# omca.net
KiCad netlist of a schematic drawn in EAGLE
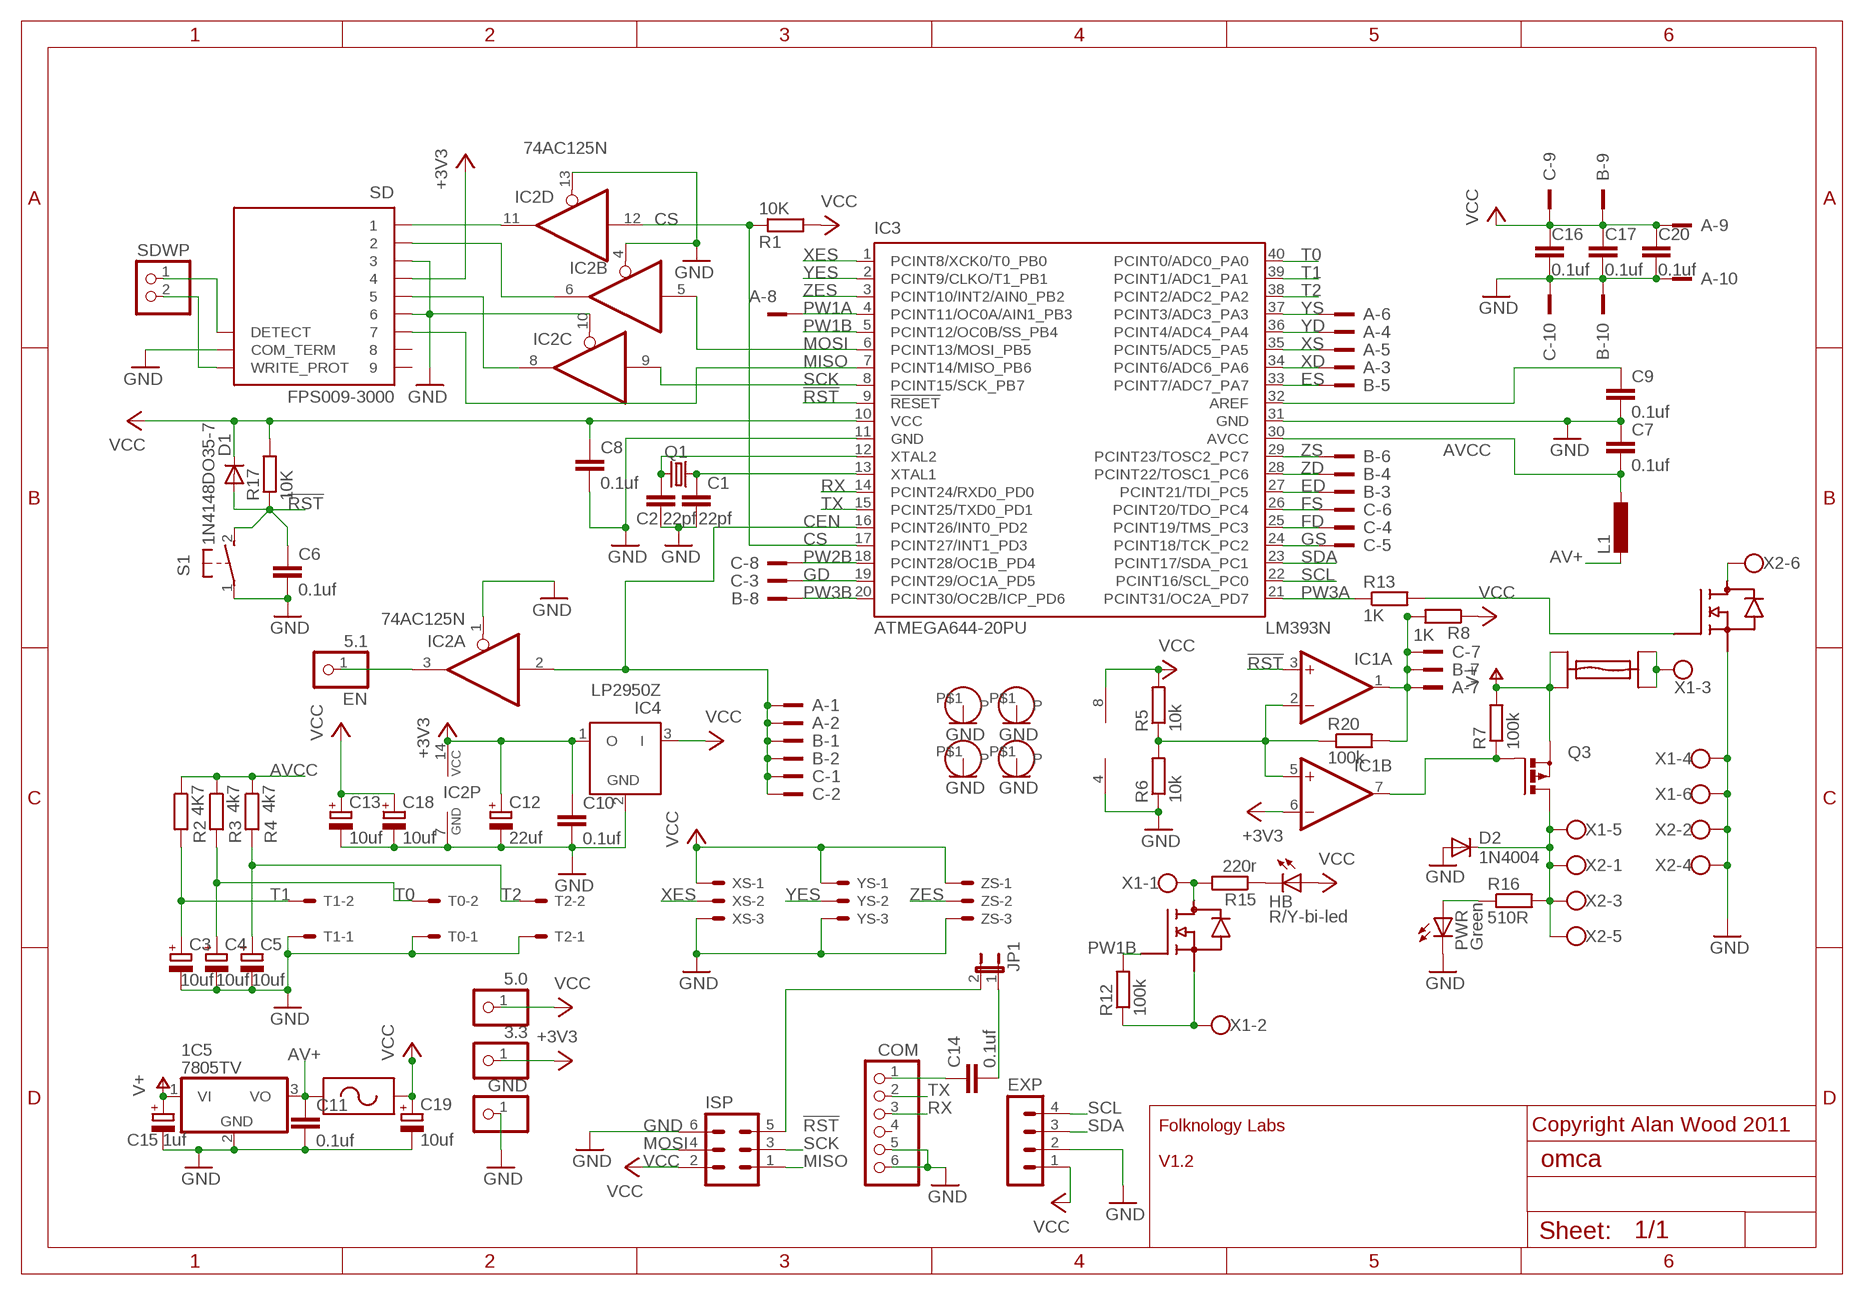
[diagram p0: schematic, sheet 1]

(export (version "E")
  (design (tool "Eeschema 10.0.6"))
  (components
    (comp (ref "1C5")
      (value "7805TV")
      (footprint "eagle-import:TO220V")
      (fields (field (name "MF") "STMICROELECTRONICS") (field (name "MPN") "L7805CV"))
      (libsource (lib "eagle-import") (part "78TV05"))
    )
    (comp (ref "3.3")
      (value "PINHD-1X1")
      (footprint "eagle-import:1X01")
      (fields (field (name "MF") "MULTICOMP") (field (name "MPN") "2211S-02G"))
      (libsource (lib "eagle-import") (part "PINHD-1X1"))
    )
    (comp (ref "5.0")
      (value "PINHD-1X1")
      (footprint "eagle-import:1X01")
      (fields (field (name "MF") "MULTICOMP") (field (name "MPN") "2211S-02G"))
      (libsource (lib "eagle-import") (part "PINHD-1X1"))
    )
    (comp (ref "5.1")
      (value "EN")
      (footprint "eagle-import:1X01")
      (fields (field (name "MF") "MULTICOMP") (field (name "MPN") "2211S-02G"))
      (libsource (lib "eagle-import") (part "PINHD-1X1"))
    )
    (comp (ref "A")
      (value "2510-5")
      (footprint "eagle-import:PAK100_2500-5-10")
      (fields
        (field (name "MF") "HARTING")
        (field (name "MPN") "09 18 510 7323")
        (field (name "OC_FARNELL") "1096980")
      )
      (libsource (lib "eagle-import") (part "2510-5"))
    )
    (comp (ref "B")
      (value "2510-5")
      (footprint "eagle-import:PAK100_2500-5-10")
      (fields
        (field (name "MF") "HARTING")
        (field (name "MPN") "09 18 510 7323")
        (field (name "OC_FARNELL") "1096980")
      )
      (libsource (lib "eagle-import") (part "2510-5"))
    )
    (comp (ref "C")
      (value "2510-5")
      (footprint "eagle-import:PAK100_2500-5-10")
      (fields
        (field (name "MF") "HARTING")
        (field (name "MPN") "09 18 510 7323")
        (field (name "OC_FARNELL") "1096980")
      )
      (libsource (lib "eagle-import") (part "2510-5"))
    )
    (comp (ref "C1")
      (value "22pf")
      (footprint "eagle-import:C025-024X044")
      (fields (field (name "MF") "AVX") (field (name "MPN") "SR151A220JAR"))
      (libsource (lib "eagle-import") (part "C-EU025-024X044"))
    )
    (comp (ref "C2")
      (value "22pf")
      (footprint "eagle-import:C025-024X044")
      (fields (field (name "MF") "AVX") (field (name "MPN") "SR151A220JAR"))
      (libsource (lib "eagle-import") (part "C-EU025-024X044"))
    )
    (comp (ref "C3")
      (value "10uf")
      (footprint "eagle-import:TT2D4")
      (fields (field (name "MF") "RUBYCON") (field (name "MPN") "100YXF10MEFC6.3X11"))
      (libsource (lib "eagle-import") (part "CPOL-EUTT2D4"))
    )
    (comp (ref "C4")
      (value "10uf")
      (footprint "eagle-import:TT2D4")
      (fields (field (name "MF") "RUBYCON") (field (name "MPN") "100YXF10MEFC6.3X11"))
      (libsource (lib "eagle-import") (part "CPOL-EUTT2D4"))
    )
    (comp (ref "C5")
      (value "10uf")
      (footprint "eagle-import:TT2D4")
      (fields (field (name "MF") "RUBYCON") (field (name "MPN") "100YXF10MEFC6.3X11"))
      (libsource (lib "eagle-import") (part "CPOL-EUTT2D4"))
    )
    (comp (ref "C6")
      (value "0.1uf")
      (footprint "eagle-import:C025-024X044")
      (fields (field (name "MF") "VISHAY") (field (name "MPN") "K104K15X7RF53L2"))
      (libsource (lib "eagle-import") (part "C-EU025-024X044"))
    )
    (comp (ref "C7")
      (value "0.1uf")
      (footprint "eagle-import:C025-024X044")
      (fields (field (name "MF") "VISHAY") (field (name "MPN") "K104K15X7RF53L2"))
      (libsource (lib "eagle-import") (part "C-EU025-024X044"))
    )
    (comp (ref "C8")
      (value "0.1uf")
      (footprint "eagle-import:C025-024X044")
      (fields (field (name "MF") "VISHAY") (field (name "MPN") "K104K15X7RF53L2"))
      (libsource (lib "eagle-import") (part "C-EU025-024X044"))
    )
    (comp (ref "C9")
      (value "0.1uf")
      (footprint "eagle-import:C025-024X044")
      (fields (field (name "MF") "VISHAY") (field (name "MPN") "K104K15X7RF53L2"))
      (libsource (lib "eagle-import") (part "C-EU025-024X044"))
    )
    (comp (ref "C10")
      (value "0.1uf")
      (footprint "eagle-import:C025-024X044")
      (fields (field (name "MF") "VISHAY") (field (name "MPN") "K104K15X7RF53L2"))
      (libsource (lib "eagle-import") (part "C-EU025-024X044"))
    )
    (comp (ref "C11")
      (value "0.1uf")
      (footprint "eagle-import:C025-024X044")
      (fields (field (name "MF") "VISHAY") (field (name "MPN") "K104K15X7RF53L2"))
      (libsource (lib "eagle-import") (part "C-EU025-024X044"))
    )
    (comp (ref "C12")
      (value "22uf")
      (footprint "eagle-import:TT2D5")
      (fields (field (name "MF") "RUBYCON") (field (name "MPN") "100YXF10MEFC6.3X11"))
      (libsource (lib "eagle-import") (part "CPOL-EUTT2D5"))
    )
    (comp (ref "C13")
      (value "10uf")
      (footprint "eagle-import:E2,5-6E")
      (fields (field (name "MF") "RUBYCON") (field (name "MPN") "25ZL47MEFC5X11"))
      (libsource (lib "eagle-import") (part "CPOL-EUE2,5-6E"))
    )
    (comp (ref "C14")
      (value "0.1uf")
      (footprint "eagle-import:C025-024X044")
      (fields (field (name "MF") "VISHAY") (field (name "MPN") "K104K15X7RF53L2"))
      (libsource (lib "eagle-import") (part "C-EU025-024X044"))
    )
    (comp (ref "C15")
      (value "1uf")
      (footprint "eagle-import:E2-4")
      (fields (field (name "MF") "RUBYCON") (field (name "MPN") "100YXF10MEFC6.3X11"))
      (libsource (lib "eagle-import") (part "CPOL-EUE2-4"))
    )
    (comp (ref "C16")
      (value "0.1uf")
      (footprint "eagle-import:C025-024X044")
      (fields (field (name "MF") "VISHAY") (field (name "MPN") "K104K15X7RF53L2"))
      (libsource (lib "eagle-import") (part "C-EU025-024X044"))
    )
    (comp (ref "C17")
      (value "0.1uf")
      (footprint "eagle-import:C025-024X044")
      (fields (field (name "MF") "VISHAY") (field (name "MPN") "K104K15X7RF53L2"))
      (libsource (lib "eagle-import") (part "C-EU025-024X044"))
    )
    (comp (ref "C18")
      (value "10uf")
      (footprint "eagle-import:E2,5-6E")
      (fields (field (name "MF") "RUBYCON") (field (name "MPN") "100YXF10MEFC6.3X11"))
      (libsource (lib "eagle-import") (part "CPOL-EUE2,5-6E"))
    )
    (comp (ref "C19")
      (value "10uf")
      (footprint "eagle-import:E2,5-6E")
      (fields (field (name "MF") "RUBYCON") (field (name "MPN") "100YXF10MEFC6.3X11"))
      (libsource (lib "eagle-import") (part "CPOL-EUE2,5-6E"))
    )
    (comp (ref "C20")
      (value "0.1uf")
      (footprint "eagle-import:C025-024X044")
      (fields (field (name "MF") "VISHAY") (field (name "MPN") "K104K15X7RF53L2"))
      (libsource (lib "eagle-import") (part "C-EU025-024X044"))
    )
    (comp (ref "COM")
      (value "PINHD-1X6/90")
      (footprint "eagle-import:1X06_90")
      (fields (field (name "MF") "MULTICOMP") (field (name "MPN") "MC34751"))
      (libsource (lib "eagle-import") (part "PINHD-1X6/90"))
    )
    (comp (ref "D1")
      (value "1N4148DO35-7")
      (footprint "eagle-import:DO35-7")
      (fields (field (name "MF") "VISHAY SEMICONDUCTOR") (field (name "MPN") "1N4148-TR"))
      (libsource (lib "eagle-import") (part "1N4148DO35-7"))
    )
    (comp (ref "D2")
      (value "1N4004")
      (footprint "eagle-import:DO41-10")
      (libsource (lib "eagle-import") (part "1N4004"))
    )
    (comp (ref "EXP")
      (value "MA04-1")
      (footprint "eagle-import:MA04-1")
      (fields
        (field (name "MF") "TE CONNECTIVITY / AMP")
        (field (name "MPN") "826926-4")
        (field (name "OC_FARNELL") "1248142")
      )
      (libsource (lib "eagle-import") (part "MA04-1"))
    )
    (comp (ref "F1")
      (value "MINIBLADEFUSEHOLDER")
      (footprint "eagle-import:MINIFUSEHOLDER")
      (libsource (lib "eagle-import") (part "MINIBLADEFUSEHOLDER"))
    )
    (comp (ref "F2")
      (value "RXEFXXX-RAYCHEM-POLYSWITCH")
      (footprint "eagle-import:2_5.1")
      (libsource (lib "eagle-import") (part "RXEFXXX-RAYCHEM-POLYSWITCH"))
    )
    (comp (ref "GND")
      (value "PINHD-1X1")
      (footprint "eagle-import:1X01")
      (fields (field (name "MF") "MULTICOMP") (field (name "MPN") "2211S-02G"))
      (libsource (lib "eagle-import") (part "PINHD-1X1"))
    )
    (comp (ref "HB")
      (value "R/Y-bi-led")
      (footprint "eagle-import:LED3MM")
      (libsource (lib "eagle-import") (part "LED3MM"))
    )
    (comp (ref "IC1")
      (value "LM393N")
      (footprint "eagle-import:DIL08")
      (fields
        (field (name "MF") "ON SEMICONDUCTOR")
        (field (name "MPN") "LM393NG")
        (field (name "OC_FARNELL") "1211133")
      )
      (libsource (lib "eagle-import") (part "LM393N"))
    )
    (comp (ref "IC2")
      (value "74AC125N")
      (footprint "eagle-import:DIL14")
      (fields
        (field (name "MF") "TEXAS INSTRUMENTS")
        (field (name "MPN") "SN74AHC125N")
        (field (name "OC_FARNELL") "1749617")
      )
      (libsource (lib "eagle-import") (part "74125NAC"))
    )
    (comp (ref "IC3")
      (value "ATMEGA644-20PU")
      (footprint "eagle-import:DIL40")
      (fields
        (field (name "MF") "ATMEL")
        (field (name "MPN") "ATMEGA644-20PU")
        (field (name "OC_FARNELL") "1288340")
      )
      (libsource (lib "eagle-import") (part "ATMEGA644-PU20"))
    )
    (comp (ref "IC4")
      (value "LP2950Z")
      (footprint "eagle-import:TO92")
      (fields (field (name "MF") "NATIONAL SEMICONDUCTOR") (field (name "MPN") "LP2950CZ-3.3/NOPB"))
      (libsource (lib "eagle-import") (part "LP2950Z"))
    )
    (comp (ref "ISP")
      (value "ML6")
      (footprint "eagle-import:ML6")
      (fields
        (field (name "MF") "HARTING")
        (field (name "MPN") "09 18 506 7324")
        (field (name "OC_FARNELL") "1096984")
      )
      (libsource (lib "eagle-import") (part "ML6"))
    )
    (comp (ref "JP1")
      (value "JP1E")
      (footprint "eagle-import:JP1")
      (fields (field (name "MF") "MULTICOMP") (field (name "MPN") "2211S-02G"))
      (libsource (lib "eagle-import") (part "JP1E"))
    )
    (comp (ref "L1")
      (value "L-EU0207/10")
      (footprint "eagle-import:0207_10")
      (fields (field (name "MF") "MULTICOMP") (field (name "MPN") "MCAL0410A1-101KU"))
      (libsource (lib "eagle-import") (part "L-EU0207/10"))
    )
    (comp (ref "PWR")
      (value "Green")
      (footprint "eagle-import:LED3MM")
      (libsource (lib "eagle-import") (part "LED3MM"))
    )
    (comp (ref "Q1")
      (value "CRYSTALHC49S")
      (footprint "eagle-import:HC49_S")
      (fields
        (field (name "MF") "MULTICOMP")
        (field (name "MPN") "HC49SM-3.6864-30-50-60-16-ATF")
        (field (name "OC_FARNELL") "1667008")
      )
      (libsource (lib "eagle-import") (part "CRYSTALHC49S"))
    )
    (comp (ref "Q2")
      (value "IPI80N03S4L-04TO262")
      (footprint "eagle-import:TO262")
      (libsource (lib "eagle-import") (part "IPI80N03S4L-04TO262"))
    )
    (comp (ref "Q3")
      (value "PMOSFET_PTO220BV")
      (footprint "eagle-import:TO220BV")
      (fields (field (name "MF") "VISHAY") (field (name "MPN") "SUP75P03-07-E3"))
      (libsource (lib "eagle-import") (part "PMOSFET_PTO220BV"))
    )
    (comp (ref "Q4")
      (value "NTD4963N")
      (footprint "eagle-import:IPAK")
      (libsource (lib "eagle-import") (part "NTD4963N"))
    )
    (comp (ref "R1")
      (value "10K")
      (footprint "eagle-import:0204_7")
      (fields (field (name "MF") "WELWYN") (field (name "MPN") "MFR4 10K 1%"))
      (libsource (lib "eagle-import") (part "R-EU_0204/7"))
    )
    (comp (ref "R2")
      (value "4K7")
      (footprint "eagle-import:0204_7")
      (fields (field (name "MF") "WELWYN") (field (name "MPN") "MFR4 4K7 1%"))
      (libsource (lib "eagle-import") (part "R-EU_0204/7"))
    )
    (comp (ref "R3")
      (value "4k7")
      (footprint "eagle-import:0204_7")
      (fields (field (name "MF") "WELWYN") (field (name "MPN") "MFR4 4K7 1%"))
      (libsource (lib "eagle-import") (part "R-EU_0204/7"))
    )
    (comp (ref "R4")
      (value "4k7")
      (footprint "eagle-import:0204_7")
      (fields (field (name "MF") "WELWYN") (field (name "MPN") "MFR4 4K7 1%"))
      (libsource (lib "eagle-import") (part "R-EU_0204/7"))
    )
    (comp (ref "R5")
      (value "10k")
      (footprint "eagle-import:0204_7")
      (fields (field (name "MF") "WELWYN") (field (name "MPN") "MFR4 10K 1%"))
      (libsource (lib "eagle-import") (part "R-EU_0204/7"))
    )
    (comp (ref "R6")
      (value "10k")
      (footprint "eagle-import:0204_7")
      (fields (field (name "MF") "WELWYN") (field (name "MPN") "MFR4 10K 1%"))
      (libsource (lib "eagle-import") (part "R-EU_0204/7"))
    )
    (comp (ref "R7")
      (value "100k")
      (footprint "eagle-import:0204_7")
      (fields (field (name "MF") "WELWYN") (field (name "MPN") "MFR4 100K 1%"))
      (libsource (lib "eagle-import") (part "R-EU_0204/7"))
    )
    (comp (ref "R8")
      (value "1K")
      (footprint "eagle-import:0204_7")
      (fields (field (name "MF") "WELWYN") (field (name "MPN") "MFR4 1K 1%"))
      (libsource (lib "eagle-import") (part "R-EU_0204/7"))
    )
    (comp (ref "R12")
      (value "100k")
      (footprint "eagle-import:0204_7")
      (fields (field (name "MF") "WELWYN") (field (name "MPN") "MFR4 100K 1%"))
      (libsource (lib "eagle-import") (part "R-EU_0204/7"))
    )
    (comp (ref "R13")
      (value "1K")
      (footprint "eagle-import:0204_7")
      (fields (field (name "MF") "WELWYN") (field (name "MPN") "MFR4 1K 1%"))
      (libsource (lib "eagle-import") (part "R-EU_0204/7"))
    )
    (comp (ref "R15")
      (value "220r")
      (footprint "eagle-import:0204_7")
      (fields (field (name "MF") "WELWYN") (field (name "MPN") "MFR4 470R 1%"))
      (libsource (lib "eagle-import") (part "R-EU_0204/7"))
    )
    (comp (ref "R16")
      (value "510R")
      (footprint "eagle-import:0204_7")
      (fields (field (name "MF") "WELWYN") (field (name "MPN") "MFR4 470R 1%"))
      (libsource (lib "eagle-import") (part "R-EU_0204/7"))
    )
    (comp (ref "R17")
      (value "10K")
      (footprint "eagle-import:0204_7")
      (fields (field (name "MF") "WELWYN") (field (name "MPN") "MFR4 10K 1%"))
      (libsource (lib "eagle-import") (part "R-EU_0204/7"))
    )
    (comp (ref "R20")
      (value "100k")
      (footprint "eagle-import:0204_7")
      (fields (field (name "MF") "WELWYN") (field (name "MPN") "MFR4 100K 1%"))
      (libsource (lib "eagle-import") (part "R-EU_0204/7"))
    )
    (comp (ref "S1")
      (value "31-XX")
      (footprint "eagle-import:B3F-31XX")
      (fields (field (name "MPN") "B3F-3100"))
      (libsource (lib "eagle-import") (part "31-XX"))
    )
    (comp (ref "SD")
      (value "FPS009-3000")
      (footprint "eagle-import:FPS009-3000")
      (fields
        (field (name "MF") "MULTICOMP")
        (field (name "MPN") "SDAMB-01215BT00")
        (field (name "OC_FARNELL") "9186140")
      )
      (libsource (lib "eagle-import") (part "FPS009-3000"))
    )
    (comp (ref "SDWP")
      (value "PINHD-1X2")
      (footprint "eagle-import:1X02")
      (fields (field (name "MF") "MULTICOMP") (field (name "MPN") "2211S-02G"))
      (libsource (lib "eagle-import") (part "PINHD-1X2"))
    )
    (comp (ref "T0")
      (value "22-05-7028-02")
      (footprint "eagle-import:7395-02")
      (fields
        (field (name "MF") "MOLEX")
        (field (name "MPN") "22-05-7028")
        (field (name "OC_FARNELL") "9731601")
      )
      (libsource (lib "eagle-import") (part "22-?-0205-7028"))
    )
    (comp (ref "T1")
      (value "22-05-7028-02")
      (footprint "eagle-import:7395-02")
      (fields
        (field (name "MF") "MOLEX")
        (field (name "MPN") "22-05-7028")
        (field (name "OC_FARNELL") "9731601")
      )
      (libsource (lib "eagle-import") (part "22-?-0205-7028"))
    )
    (comp (ref "T2")
      (value "22-05-7028-02")
      (footprint "eagle-import:7395-02")
      (fields
        (field (name "MF") "MOLEX")
        (field (name "MPN") "22-05-7028")
        (field (name "OC_FARNELL") "9731601")
      )
      (libsource (lib "eagle-import") (part "22-?-0205-7028"))
    )
    (comp (ref "U$2")
      (value "HOLE")
      (footprint "eagle-import:HOLE")
      (libsource (lib "eagle-import") (part "HOLE"))
    )
    (comp (ref "U$3")
      (value "HOLE")
      (footprint "eagle-import:HOLE")
      (libsource (lib "eagle-import") (part "HOLE"))
    )
    (comp (ref "U$4")
      (value "HOLE")
      (footprint "eagle-import:HOLE")
      (libsource (lib "eagle-import") (part "HOLE"))
    )
    (comp (ref "U$5")
      (value "HOLE")
      (footprint "eagle-import:HOLE")
      (libsource (lib "eagle-import") (part "HOLE"))
    )
    (comp (ref "X1")
      (value "W237-6")
      (footprint "eagle-import:W237-6")
      (libsource (lib "eagle-import") (part "W237-6"))
    )
    (comp (ref "X2")
      (value "W237-6")
      (footprint "eagle-import:W237-6")
      (libsource (lib "eagle-import") (part "W237-6"))
    )
    (comp (ref "XS")
      (value "22-05-7038-03")
      (footprint "eagle-import:7395-03")
      (fields
        (field (name "MF") "MOLEX")
        (field (name "MPN") "22-05-7038")
        (field (name "OC_FARNELL") "9731610")
      )
      (libsource (lib "eagle-import") (part "22-?-0305-7038"))
    )
    (comp (ref "YS")
      (value "22-05-7038-03")
      (footprint "eagle-import:7395-03")
      (fields
        (field (name "MF") "MOLEX")
        (field (name "MPN") "22-05-7038")
        (field (name "OC_FARNELL") "9731610")
      )
      (libsource (lib "eagle-import") (part "22-?-0305-7038"))
    )
    (comp (ref "ZS")
      (value "22-05-7038-03")
      (footprint "eagle-import:7395-03")
      (fields
        (field (name "MF") "MOLEX")
        (field (name "MPN") "22-05-7038")
        (field (name "OC_FARNELL") "9731610")
      )
      (libsource (lib "eagle-import") (part "22-?-0305-7038"))
    )
  )
  (nets
    (net (code "1") (name "+3V3") (class "Default")
      (node (ref "3.3") (pin "1") (pinfunction "1_1") (pintype "passive"))
      (node (ref "C10") (pin "1") (pinfunction "1_1") (pintype "passive"))
      (node (ref "C12") (pin "+") (pinfunction "+_+") (pintype "passive"))
      (node (ref "IC1") (pin "6") (pinfunction "-IN_6") (pintype "input"))
      (node (ref "IC2") (pin "14") (pinfunction "VCC_14") (pintype "power_in"))
      (node (ref "IC4") (pin "1") (pinfunction "O_1") (pintype "input"))
      (node (ref "SD") (pin "4") (pinfunction "4_4") (pintype "input"))
    )
    (net (code "2") (name "/AV+") (class "Default")
      (node (ref "1C5") (pin "3") (pinfunction "VO_3") (pintype "passive"))
      (node (ref "C11") (pin "1") (pinfunction "1_1") (pintype "passive"))
      (node (ref "F2") (pin "P$1") (pinfunction "P$1_P$1") (pintype "passive"))
      (node (ref "L1") (pin "2") (pinfunction "2_2") (pintype "passive"))
    )
    (net (code "3") (name "/AVCC") (class "Default")
      (node (ref "C7") (pin "2") (pinfunction "2_2") (pintype "passive"))
      (node (ref "IC3") (pin "30") (pinfunction "AVCC_30") (pintype "power_in"))
      (node (ref "L1") (pin "1") (pinfunction "1_1") (pintype "passive"))
      (node (ref "R2") (pin "1") (pinfunction "1_1") (pintype "passive"))
      (node (ref "R3") (pin "1") (pinfunction "1_1") (pintype "passive"))
      (node (ref "R4") (pin "1") (pinfunction "1_1") (pintype "passive"))
    )
    (net (code "4") (name "/CEN") (class "Default")
      (node (ref "A") (pin "1") (pinfunction "KL_1") (pintype "passive"))
      (node (ref "A") (pin "2") (pinfunction "KL_2") (pintype "passive"))
      (node (ref "B") (pin "1") (pinfunction "KL_1") (pintype "passive"))
      (node (ref "B") (pin "2") (pinfunction "KL_2") (pintype "passive"))
      (node (ref "C") (pin "1") (pinfunction "KL_1") (pintype "passive"))
      (node (ref "C") (pin "2") (pinfunction "KL_2") (pintype "passive"))
      (node (ref "IC2") (pin "2") (pinfunction "I_2") (pintype "input"))
      (node (ref "IC3") (pin "16") (pinfunction "PCINT26/INT0_PD2_16") (pintype "bidirectional"))
    )
    (net (code "5") (name "/CS") (class "Default")
      (node (ref "IC2") (pin "12") (pinfunction "I_12") (pintype "input"))
      (node (ref "IC3") (pin "17") (pinfunction "PCINT27/INT1_PD3_17") (pintype "bidirectional"))
      (node (ref "R1") (pin "1") (pinfunction "1_1") (pintype "passive"))
    )
    (net (code "6") (name "/ED") (class "Default")
      (node (ref "B") (pin "3") (pinfunction "KL_3") (pintype "passive"))
      (node (ref "IC3") (pin "27") (pinfunction "PCINT21/TDI_PC5_27") (pintype "bidirectional"))
    )
    (net (code "7") (name "/ES") (class "Default")
      (node (ref "B") (pin "5") (pinfunction "KL_5") (pintype "passive"))
      (node (ref "IC3") (pin "33") (pinfunction "PCINT7/ADC7_PA7_33") (pintype "bidirectional"))
    )
    (net (code "8") (name "/FD") (class "Default")
      (node (ref "C") (pin "4") (pinfunction "KL_4") (pintype "passive"))
      (node (ref "IC3") (pin "25") (pinfunction "PCINT19/TMS_PC3_25") (pintype "bidirectional"))
    )
    (net (code "9") (name "/FS") (class "Default")
      (node (ref "C") (pin "6") (pinfunction "KL_6") (pintype "passive"))
      (node (ref "IC3") (pin "26") (pinfunction "PCINT20/TDO_PC4_26") (pintype "bidirectional"))
    )
    (net (code "10") (name "/GD") (class "Default")
      (node (ref "C") (pin "3") (pinfunction "KL_3") (pintype "passive"))
      (node (ref "IC3") (pin "19") (pinfunction "PCINT29/OC1A_PD5_19") (pintype "bidirectional"))
    )
    (net (code "11") (name "/GS") (class "Default")
      (node (ref "C") (pin "5") (pinfunction "KL_5") (pintype "passive"))
      (node (ref "IC3") (pin "24") (pinfunction "PCINT18/TCK_PC2_24") (pintype "bidirectional"))
    )
    (net (code "12") (name "/MISO") (class "Default")
      (node (ref "IC3") (pin "7") (pinfunction "PCINT14/MISO_PB6_7") (pintype "bidirectional"))
      (node (ref "ISP") (pin "1") (pinfunction "1_1") (pintype "passive"))
      (node (ref "SD") (pin "7") (pinfunction "7_7") (pintype "input"))
    )
    (net (code "13") (name "/MOSI") (class "Default")
      (node (ref "IC2") (pin "5") (pinfunction "I_5") (pintype "input"))
      (node (ref "IC3") (pin "6") (pinfunction "PCINT13/MOSI_PB5_6") (pintype "bidirectional"))
      (node (ref "ISP") (pin "4") (pinfunction "4_4") (pintype "passive"))
    )
    (net (code "14") (name "/PW1A") (class "Default")
      (node (ref "A") (pin "8") (pinfunction "KL_8") (pintype "passive"))
      (node (ref "IC3") (pin "4") (pinfunction "PCINT11/OC0A/AIN1_PB3_4") (pintype "bidirectional"))
    )
    (net (code "15") (name "/PW1B") (class "Default")
      (node (ref "IC3") (pin "5") (pinfunction "PCINT12/OC0B/SS_PB4_5") (pintype "bidirectional"))
      (node (ref "Q2") (pin "1") (pinfunction "G_1") (pintype "passive"))
      (node (ref "R12") (pin "2") (pinfunction "2_2") (pintype "passive"))
    )
    (net (code "16") (name "/PW2B") (class "Default")
      (node (ref "C") (pin "8") (pinfunction "KL_8") (pintype "passive"))
      (node (ref "IC3") (pin "18") (pinfunction "PCINT28/OC1B_PD4_18") (pintype "bidirectional"))
    )
    (net (code "17") (name "/PW3A") (class "Default")
      (node (ref "IC3") (pin "21") (pinfunction "PCINT31/OC2A_PD7_21") (pintype "bidirectional"))
      (node (ref "R13") (pin "1") (pinfunction "1_1") (pintype "passive"))
    )
    (net (code "18") (name "/PW3B") (class "Default")
      (node (ref "B") (pin "8") (pinfunction "KL_8") (pintype "passive"))
      (node (ref "IC3") (pin "20") (pinfunction "PCINT30/OC2B/ICP_PD6_20") (pintype "bidirectional"))
    )
    (net (code "19") (name "/RX") (class "Default")
      (node (ref "COM") (pin "3") (pinfunction "3_3") (pintype "passive"))
      (node (ref "IC3") (pin "14") (pinfunction "PCINT24/RXD0_PD0_14") (pintype "bidirectional"))
    )
    (net (code "20") (name "/SCK") (class "Default")
      (node (ref "IC2") (pin "9") (pinfunction "I_9") (pintype "input"))
      (node (ref "IC3") (pin "8") (pinfunction "PCINT15/SCK_PB7_8") (pintype "bidirectional"))
      (node (ref "ISP") (pin "3") (pinfunction "3_3") (pintype "passive"))
    )
    (net (code "21") (name "/SCL") (class "Default")
      (node (ref "EXP") (pin "4") (pinfunction "4_4") (pintype "passive"))
      (node (ref "IC3") (pin "22") (pinfunction "PCINT16/SCL_PC0_22") (pintype "bidirectional"))
    )
    (net (code "22") (name "/SDA") (class "Default")
      (node (ref "EXP") (pin "3") (pinfunction "3_3") (pintype "passive"))
      (node (ref "IC3") (pin "23") (pinfunction "PCINT17/SDA_PC1_23") (pintype "bidirectional"))
    )
    (net (code "23") (name "/T0") (class "Default")
      (node (ref "C4") (pin "+") (pinfunction "+_+") (pintype "passive"))
      (node (ref "IC3") (pin "40") (pinfunction "PCINT0/ADC0_PA0_40") (pintype "bidirectional"))
      (node (ref "R3") (pin "2") (pinfunction "2_2") (pintype "passive"))
      (node (ref "T0") (pin "2") (pinfunction "S_2") (pintype "passive"))
    )
    (net (code "24") (name "/T1") (class "Default")
      (node (ref "C3") (pin "+") (pinfunction "+_+") (pintype "passive"))
      (node (ref "IC3") (pin "39") (pinfunction "PCINT1/ADC1_PA1_39") (pintype "bidirectional"))
      (node (ref "R2") (pin "2") (pinfunction "2_2") (pintype "passive"))
      (node (ref "T1") (pin "2") (pinfunction "S_2") (pintype "passive"))
    )
    (net (code "25") (name "/T2") (class "Default")
      (node (ref "C5") (pin "+") (pinfunction "+_+") (pintype "passive"))
      (node (ref "IC3") (pin "38") (pinfunction "PCINT2/ADC2_PA2_38") (pintype "bidirectional"))
      (node (ref "R4") (pin "2") (pinfunction "2_2") (pintype "passive"))
      (node (ref "T2") (pin "2") (pinfunction "S_2") (pintype "passive"))
    )
    (net (code "26") (name "/TX") (class "Default")
      (node (ref "COM") (pin "2") (pinfunction "2_2") (pintype "passive"))
      (node (ref "IC3") (pin "15") (pinfunction "PCINT25/TXD0_PD1_15") (pintype "bidirectional"))
    )
    (net (code "27") (name "/XD") (class "Default")
      (node (ref "A") (pin "3") (pinfunction "KL_3") (pintype "passive"))
      (node (ref "IC3") (pin "34") (pinfunction "PCINT6/ADC6_PA6_34") (pintype "bidirectional"))
    )
    (net (code "28") (name "/XES") (class "Default")
      (node (ref "IC3") (pin "1") (pinfunction "PCINT8/XCK0/T0_PB0_1") (pintype "bidirectional"))
      (node (ref "XS") (pin "2") (pinfunction "S_2") (pintype "passive"))
    )
    (net (code "29") (name "/XS") (class "Default")
      (node (ref "A") (pin "5") (pinfunction "KL_5") (pintype "passive"))
      (node (ref "IC3") (pin "35") (pinfunction "PCINT5/ADC5_PA5_35") (pintype "bidirectional"))
    )
    (net (code "30") (name "/YD") (class "Default")
      (node (ref "A") (pin "4") (pinfunction "KL_4") (pintype "passive"))
      (node (ref "IC3") (pin "36") (pinfunction "PCINT4/ADC4_PA4_36") (pintype "bidirectional"))
    )
    (net (code "31") (name "/YES") (class "Default")
      (node (ref "IC3") (pin "2") (pinfunction "PCINT9/CLKO/T1_PB1_2") (pintype "bidirectional"))
      (node (ref "YS") (pin "2") (pinfunction "S_2") (pintype "passive"))
    )
    (net (code "32") (name "/YS") (class "Default")
      (node (ref "A") (pin "6") (pinfunction "KL_6") (pintype "passive"))
      (node (ref "IC3") (pin "37") (pinfunction "PCINT3/ADC3_PA3_37") (pintype "bidirectional"))
    )
    (net (code "33") (name "/ZD") (class "Default")
      (node (ref "B") (pin "4") (pinfunction "KL_4") (pintype "passive"))
      (node (ref "IC3") (pin "28") (pinfunction "PCINT22/TOSC1_PC6_28") (pintype "bidirectional"))
    )
    (net (code "34") (name "/ZES") (class "Default")
      (node (ref "IC3") (pin "3") (pinfunction "PCINT10/INT2/AIN0_PB2_3") (pintype "bidirectional"))
      (node (ref "ZS") (pin "2") (pinfunction "S_2") (pintype "passive"))
    )
    (net (code "35") (name "/ZS") (class "Default")
      (node (ref "B") (pin "6") (pinfunction "KL_6") (pintype "passive"))
      (node (ref "IC3") (pin "29") (pinfunction "PCINT23/TOSC2_PC7_29") (pintype "bidirectional"))
    )
    (net (code "36") (name "/~{RST}") (class "Default")
      (node (ref "C6") (pin "1") (pinfunction "1_1") (pintype "passive"))
      (node (ref "D1") (pin "A") (pinfunction "A_A") (pintype "passive"))
      (node (ref "IC1") (pin "3") (pinfunction "+IN_3") (pintype "input"))
      (node (ref "IC3") (pin "9") (pinfunction "~{RESET}_9") (pintype "input"))
      (node (ref "ISP") (pin "5") (pinfunction "5_5") (pintype "passive"))
      (node (ref "JP1") (pin "2") (pinfunction "2_2") (pintype "passive"))
      (node (ref "R17") (pin "1") (pinfunction "1_1") (pintype "passive"))
      (node (ref "S1") (pin "2") (pinfunction "S_2") (pintype "passive"))
    )
    (net (code "37") (name "GND") (class "Default")
      (node (ref "1C5") (pin "2") (pinfunction "GND_2") (pintype "passive"))
      (node (ref "A") (pin "10") (pinfunction "KL_10") (pintype "passive"))
      (node (ref "B") (pin "10") (pinfunction "KL_10") (pintype "passive"))
      (node (ref "C") (pin "10") (pinfunction "KL_10") (pintype "passive"))
      (node (ref "C1") (pin "2") (pinfunction "2_2") (pintype "passive"))
      (node (ref "C10") (pin "2") (pinfunction "2_2") (pintype "passive"))
      (node (ref "C11") (pin "2") (pinfunction "2_2") (pintype "passive"))
      (node (ref "C12") (pin "-") (pinfunction "-_-") (pintype "passive"))
      (node (ref "C13") (pin "-") (pinfunction "-_-") (pintype "passive"))
      (node (ref "C15") (pin "-") (pinfunction "-_-") (pintype "passive"))
      (node (ref "C16") (pin "2") (pinfunction "2_2") (pintype "passive"))
      (node (ref "C17") (pin "2") (pinfunction "2_2") (pintype "passive"))
      (node (ref "C18") (pin "-") (pinfunction "-_-") (pintype "passive"))
      (node (ref "C19") (pin "-") (pinfunction "-_-") (pintype "passive"))
      (node (ref "C2") (pin "2") (pinfunction "2_2") (pintype "passive"))
      (node (ref "C20") (pin "2") (pinfunction "2_2") (pintype "passive"))
      (node (ref "C3") (pin "-") (pinfunction "-_-") (pintype "passive"))
      (node (ref "C4") (pin "-") (pinfunction "-_-") (pintype "passive"))
      (node (ref "C5") (pin "-") (pinfunction "-_-") (pintype "passive"))
      (node (ref "C6") (pin "2") (pinfunction "2_2") (pintype "passive"))
      (node (ref "C7") (pin "1") (pinfunction "1_1") (pintype "passive"))
      (node (ref "C8") (pin "2") (pinfunction "2_2") (pintype "passive"))
      (node (ref "C9") (pin "2") (pinfunction "2_2") (pintype "passive"))
      (node (ref "COM") (pin "5") (pinfunction "5_5") (pintype "passive"))
      (node (ref "COM") (pin "6") (pinfunction "6_6") (pintype "passive"))
      (node (ref "D2") (pin "A") (pinfunction "A_A") (pintype "passive"))
      (node (ref "EXP") (pin "2") (pinfunction "2_2") (pintype "passive"))
      (node (ref "GND") (pin "1") (pinfunction "1_1") (pintype "passive"))
      (node (ref "IC1") (pin "4") (pinfunction "V-_4") (pintype "power_in"))
      (node (ref "IC2") (pin "1") (pinfunction "OE_1") (pintype "input"))
      (node (ref "IC2") (pin "10") (pinfunction "OE_10") (pintype "input"))
      (node (ref "IC2") (pin "13") (pinfunction "OE_13") (pintype "input"))
      (node (ref "IC2") (pin "4") (pinfunction "OE_4") (pintype "input"))
      (node (ref "IC2") (pin "7") (pinfunction "GND_7") (pintype "power_in"))
      (node (ref "IC3") (pin "11") (pinfunction "GND_11") (pintype "power_in"))
      (node (ref "IC3") (pin "31") (pinfunction "GND_31") (pintype "power_in"))
      (node (ref "IC4") (pin "2") (pinfunction "GND_2") (pintype "power_in"))
      (node (ref "ISP") (pin "6") (pinfunction "6_6") (pintype "passive"))
      (node (ref "PWR") (pin "K") (pinfunction "C_K") (pintype "passive"))
      (node (ref "Q4") (pin "P$3") (pinfunction "S_P$3") (pintype "passive"))
      (node (ref "R6") (pin "1") (pinfunction "1_1") (pintype "passive"))
      (node (ref "S1") (pin "1") (pinfunction "P_1") (pintype "passive"))
      (node (ref "SD") (pin "3") (pinfunction "3_3") (pintype "input"))
      (node (ref "SD") (pin "6") (pinfunction "6_6") (pintype "input"))
      (node (ref "SD") (pin "COM_TERM") (pinfunction "COM_TERM_COM_TERM") (pintype "input"))
      (node (ref "T0") (pin "1") (pinfunction "S_1") (pintype "passive"))
      (node (ref "T1") (pin "1") (pinfunction "S_1") (pintype "passive"))
      (node (ref "T2") (pin "1") (pinfunction "S_1") (pintype "passive"))
      (node (ref "U$2") (pin "P$1") (pinfunction "P_P$1") (pintype "bidirectional"))
      (node (ref "U$3") (pin "P$1") (pinfunction "P_P$1") (pintype "bidirectional"))
      (node (ref "U$4") (pin "P$1") (pinfunction "P_P$1") (pintype "bidirectional"))
      (node (ref "U$5") (pin "P$1") (pinfunction "P_P$1") (pintype "bidirectional"))
      (node (ref "X1") (pin "4") (pinfunction "KL_4") (pintype "passive"))
      (node (ref "X1") (pin "6") (pinfunction "KL_6") (pintype "passive"))
      (node (ref "X2") (pin "2") (pinfunction "KL_2") (pintype "passive"))
      (node (ref "X2") (pin "4") (pinfunction "KL_4") (pintype "passive"))
      (node (ref "XS") (pin "3") (pinfunction "S_3") (pintype "passive"))
      (node (ref "YS") (pin "3") (pinfunction "S_3") (pintype "passive"))
      (node (ref "ZS") (pin "3") (pinfunction "S_3") (pintype "passive"))
    )
    (net (code "38") (name "Net-(AH-KL)") (class "Default")
      (node (ref "A") (pin "7") (pinfunction "KL_7") (pintype "passive"))
      (node (ref "B") (pin "7") (pinfunction "KL_7") (pintype "passive"))
      (node (ref "C") (pin "7") (pinfunction "KL_7") (pintype "passive"))
      (node (ref "IC1") (pin "1") (pinfunction "OUT_1") (pintype "output"))
      (node (ref "R20") (pin "2") (pinfunction "2_2") (pintype "passive"))
      (node (ref "R8") (pin "2") (pinfunction "2_2") (pintype "passive"))
    )
    (net (code "39") (name "Net-(C14-Pad1)") (class "Default")
      (node (ref "C14") (pin "1") (pinfunction "1_1") (pintype "passive"))
      (node (ref "COM") (pin "1") (pinfunction "1_1") (pintype "passive"))
    )
    (net (code "40") (name "Net-(C14-Pad2)") (class "Default")
      (node (ref "C14") (pin "2") (pinfunction "2_2") (pintype "passive"))
      (node (ref "JP1") (pin "1") (pinfunction "1_1") (pintype "passive"))
    )
    (net (code "41") (name "Net-(F1-F1A)") (class "Default")
      (node (ref "F1") (pin "P$1") (pinfunction "F1A_P$1") (pintype "passive"))
      (node (ref "F1") (pin "P$2") (pinfunction "F1B_P$2") (pintype "passive"))
      (node (ref "X1") (pin "3") (pinfunction "KL_3") (pintype "passive"))
    )
    (net (code "42") (name "Net-(HB-C)") (class "Default")
      (node (ref "HB") (pin "K") (pinfunction "C_K") (pintype "passive"))
      (node (ref "R15") (pin "1") (pinfunction "1_1") (pintype "passive"))
    )
    (net (code "43") (name "Net-(IC1A--IN)") (class "Default")
      (node (ref "IC1") (pin "2") (pinfunction "-IN_2") (pintype "input"))
      (node (ref "IC1") (pin "5") (pinfunction "+IN_5") (pintype "input"))
      (node (ref "R20") (pin "1") (pinfunction "1_1") (pintype "passive"))
      (node (ref "R5") (pin "1") (pinfunction "1_1") (pintype "passive"))
      (node (ref "R6") (pin "2") (pinfunction "2_2") (pintype "passive"))
    )
    (net (code "44") (name "Net-(IC1B-OUT)") (class "Default")
      (node (ref "IC1") (pin "7") (pinfunction "OUT_7") (pintype "output"))
      (node (ref "Q3") (pin "G") (pinfunction "G_G") (pintype "passive"))
      (node (ref "R7") (pin "1") (pinfunction "1_1") (pintype "passive"))
    )
    (net (code "45") (name "Net-(IC2A-O)") (class "Default")
      (node (ref "5.1") (pin "1") (pinfunction "1_1") (pintype "passive"))
      (node (ref "IC2") (pin "3") (pinfunction "O_3") (pintype "tri_state"))
    )
    (net (code "46") (name "Net-(IC2B-O)") (class "Default")
      (node (ref "IC2") (pin "6") (pinfunction "O_6") (pintype "tri_state"))
      (node (ref "SD") (pin "2") (pinfunction "2_2") (pintype "input"))
    )
    (net (code "47") (name "Net-(IC2C-O)") (class "Default")
      (node (ref "IC2") (pin "8") (pinfunction "O_8") (pintype "tri_state"))
      (node (ref "SD") (pin "5") (pinfunction "5_5") (pintype "input"))
    )
    (net (code "48") (name "Net-(IC2D-O)") (class "Default")
      (node (ref "IC2") (pin "11") (pinfunction "O_11") (pintype "tri_state"))
      (node (ref "SD") (pin "1") (pinfunction "1_1") (pintype "input"))
    )
    (net (code "49") (name "Net-(IC3-AREF)") (class "Default")
      (node (ref "C9") (pin "1") (pinfunction "1_1") (pintype "passive"))
      (node (ref "IC3") (pin "32") (pinfunction "AREF_32") (pintype "passive"))
    )
    (net (code "50") (name "Net-(IC3-XTAL1)") (class "Default")
      (node (ref "C1") (pin "1") (pinfunction "1_1") (pintype "passive"))
      (node (ref "IC3") (pin "13") (pinfunction "XTAL1_13") (pintype "input"))
      (node (ref "Q1") (pin "1") (pinfunction "1_1") (pintype "passive"))
    )
    (net (code "51") (name "Net-(IC3-XTAL2)") (class "Default")
      (node (ref "C2") (pin "1") (pinfunction "1_1") (pintype "passive"))
      (node (ref "IC3") (pin "12") (pinfunction "XTAL2_12") (pintype "output"))
      (node (ref "Q1") (pin "2") (pinfunction "2_2") (pintype "passive"))
    )
    (net (code "52") (name "Net-(PWR-PadA)") (class "Default")
      (node (ref "PWR") (pin "A") (pinfunction "A_A") (pintype "passive"))
      (node (ref "R16") (pin "1") (pinfunction "1_1") (pintype "passive"))
    )
    (net (code "53") (name "Net-(Q2-D)") (class "Default")
      (node (ref "Q2") (pin "2") (pinfunction "D_2") (pintype "passive"))
      (node (ref "R15") (pin "2") (pinfunction "2_2") (pintype "passive"))
      (node (ref "X1") (pin "1") (pinfunction "KL_1") (pintype "passive"))
    )
    (net (code "54") (name "Net-(Q2-S)") (class "Default")
      (node (ref "Q2") (pin "3") (pinfunction "S_3") (pintype "passive"))
      (node (ref "R12") (pin "1") (pinfunction "1_1") (pintype "passive"))
      (node (ref "X1") (pin "2") (pinfunction "KL_2") (pintype "passive"))
    )
    (net (code "55") (name "Net-(Q4-D)") (class "Default")
      (node (ref "Q4") (pin "P$2") (pinfunction "D_P$2") (pintype "passive"))
      (node (ref "X2") (pin "6") (pinfunction "KL_6") (pintype "passive"))
    )
    (net (code "56") (name "Net-(Q4-G)") (class "Default")
      (node (ref "Q4") (pin "P$1") (pinfunction "G_P$1") (pintype "passive"))
      (node (ref "R13") (pin "2") (pinfunction "2_2") (pintype "passive"))
    )
    (net (code "57") (name "Net-(SD-PadDETECT)") (class "Default")
      (node (ref "SD") (pin "DETECT") (pinfunction "DETECT_DETECT") (pintype "input"))
      (node (ref "SDWP") (pin "1") (pinfunction "1_1") (pintype "passive"))
    )
    (net (code "58") (name "Net-(SD-PadWRITE_PROT)") (class "Default")
      (node (ref "SD") (pin "WRITE_PROT") (pinfunction "WRITE_PROT_WRITE_PROT") (pintype "input"))
      (node (ref "SDWP") (pin "2") (pinfunction "2_2") (pintype "passive"))
    )
    (net (code "59") (name "Net-(X1E-KL)") (class "Default")
      (node (ref "D2") (pin "C") (pinfunction "C_C") (pintype "passive"))
      (node (ref "Q3") (pin "D") (pinfunction "D_D") (pintype "passive"))
      (node (ref "R16") (pin "2") (pinfunction "2_2") (pintype "passive"))
      (node (ref "X1") (pin "5") (pinfunction "KL_5") (pintype "passive"))
      (node (ref "X2") (pin "1") (pinfunction "KL_1") (pintype "passive"))
      (node (ref "X2") (pin "3") (pinfunction "KL_3") (pintype "passive"))
      (node (ref "X2") (pin "5") (pinfunction "KL_5") (pintype "passive"))
    )
    (net (code "60") (name "V+") (class "Default")
      (node (ref "1C5") (pin "1") (pinfunction "VI_1") (pintype "input"))
      (node (ref "C15") (pin "+") (pinfunction "+_+") (pintype "passive"))
      (node (ref "F1") (pin "P$3") (pinfunction "F2A_P$3") (pintype "passive"))
      (node (ref "F1") (pin "P$4") (pinfunction "F2B_P$4") (pintype "passive"))
      (node (ref "Q3") (pin "S") (pinfunction "S_S") (pintype "passive"))
      (node (ref "R7") (pin "2") (pinfunction "2_2") (pintype "passive"))
    )
    (net (code "61") (name "VCC") (class "Default")
      (node (ref "5.0") (pin "1") (pinfunction "1_1") (pintype "passive"))
      (node (ref "A") (pin "9") (pinfunction "KL_9") (pintype "passive"))
      (node (ref "B") (pin "9") (pinfunction "KL_9") (pintype "passive"))
      (node (ref "C") (pin "9") (pinfunction "KL_9") (pintype "passive"))
      (node (ref "C13") (pin "+") (pinfunction "+_+") (pintype "passive"))
      (node (ref "C16") (pin "1") (pinfunction "1_1") (pintype "passive"))
      (node (ref "C17") (pin "1") (pinfunction "1_1") (pintype "passive"))
      (node (ref "C18") (pin "+") (pinfunction "+_+") (pintype "passive"))
      (node (ref "C19") (pin "+") (pinfunction "+_+") (pintype "passive"))
      (node (ref "C20") (pin "1") (pinfunction "1_1") (pintype "passive"))
      (node (ref "C8") (pin "1") (pinfunction "1_1") (pintype "passive"))
      (node (ref "D1") (pin "C") (pinfunction "C_C") (pintype "passive"))
      (node (ref "EXP") (pin "1") (pinfunction "1_1") (pintype "passive"))
      (node (ref "F2") (pin "P$2") (pinfunction "P$2_P$2") (pintype "passive"))
      (node (ref "HB") (pin "A") (pinfunction "A_A") (pintype "passive"))
      (node (ref "IC1") (pin "8") (pinfunction "V+_8") (pintype "power_in"))
      (node (ref "IC3") (pin "10") (pinfunction "VCC_10") (pintype "power_in"))
      (node (ref "IC4") (pin "3") (pinfunction "I_3") (pintype "input"))
      (node (ref "ISP") (pin "2") (pinfunction "2_2") (pintype "passive"))
      (node (ref "R1") (pin "2") (pinfunction "2_2") (pintype "passive"))
      (node (ref "R17") (pin "2") (pinfunction "2_2") (pintype "passive"))
      (node (ref "R5") (pin "2") (pinfunction "2_2") (pintype "passive"))
      (node (ref "R8") (pin "1") (pinfunction "1_1") (pintype "passive"))
      (node (ref "XS") (pin "1") (pinfunction "S_1") (pintype "passive"))
      (node (ref "YS") (pin "1") (pinfunction "S_1") (pintype "passive"))
      (node (ref "ZS") (pin "1") (pinfunction "S_1") (pintype "passive"))
    )
    (net (code "62") (name "unconnected-(COM-Pad4)") (class "Default")
      (node (ref "COM") (pin "4") (pinfunction "4_4") (pintype "passive"))
    )
    (net (code "63") (name "unconnected-(SD-Pad8)") (class "Default")
      (node (ref "SD") (pin "8") (pinfunction "8_8") (pintype "input"))
    )
    (net (code "64") (name "unconnected-(SD-Pad9)") (class "Default")
      (node (ref "SD") (pin "9") (pinfunction "9_9") (pintype "input"))
    )
  )
)
